# test_for_1_69.net
KiCad netlist of a schematic drawn in EasyEDA Pro
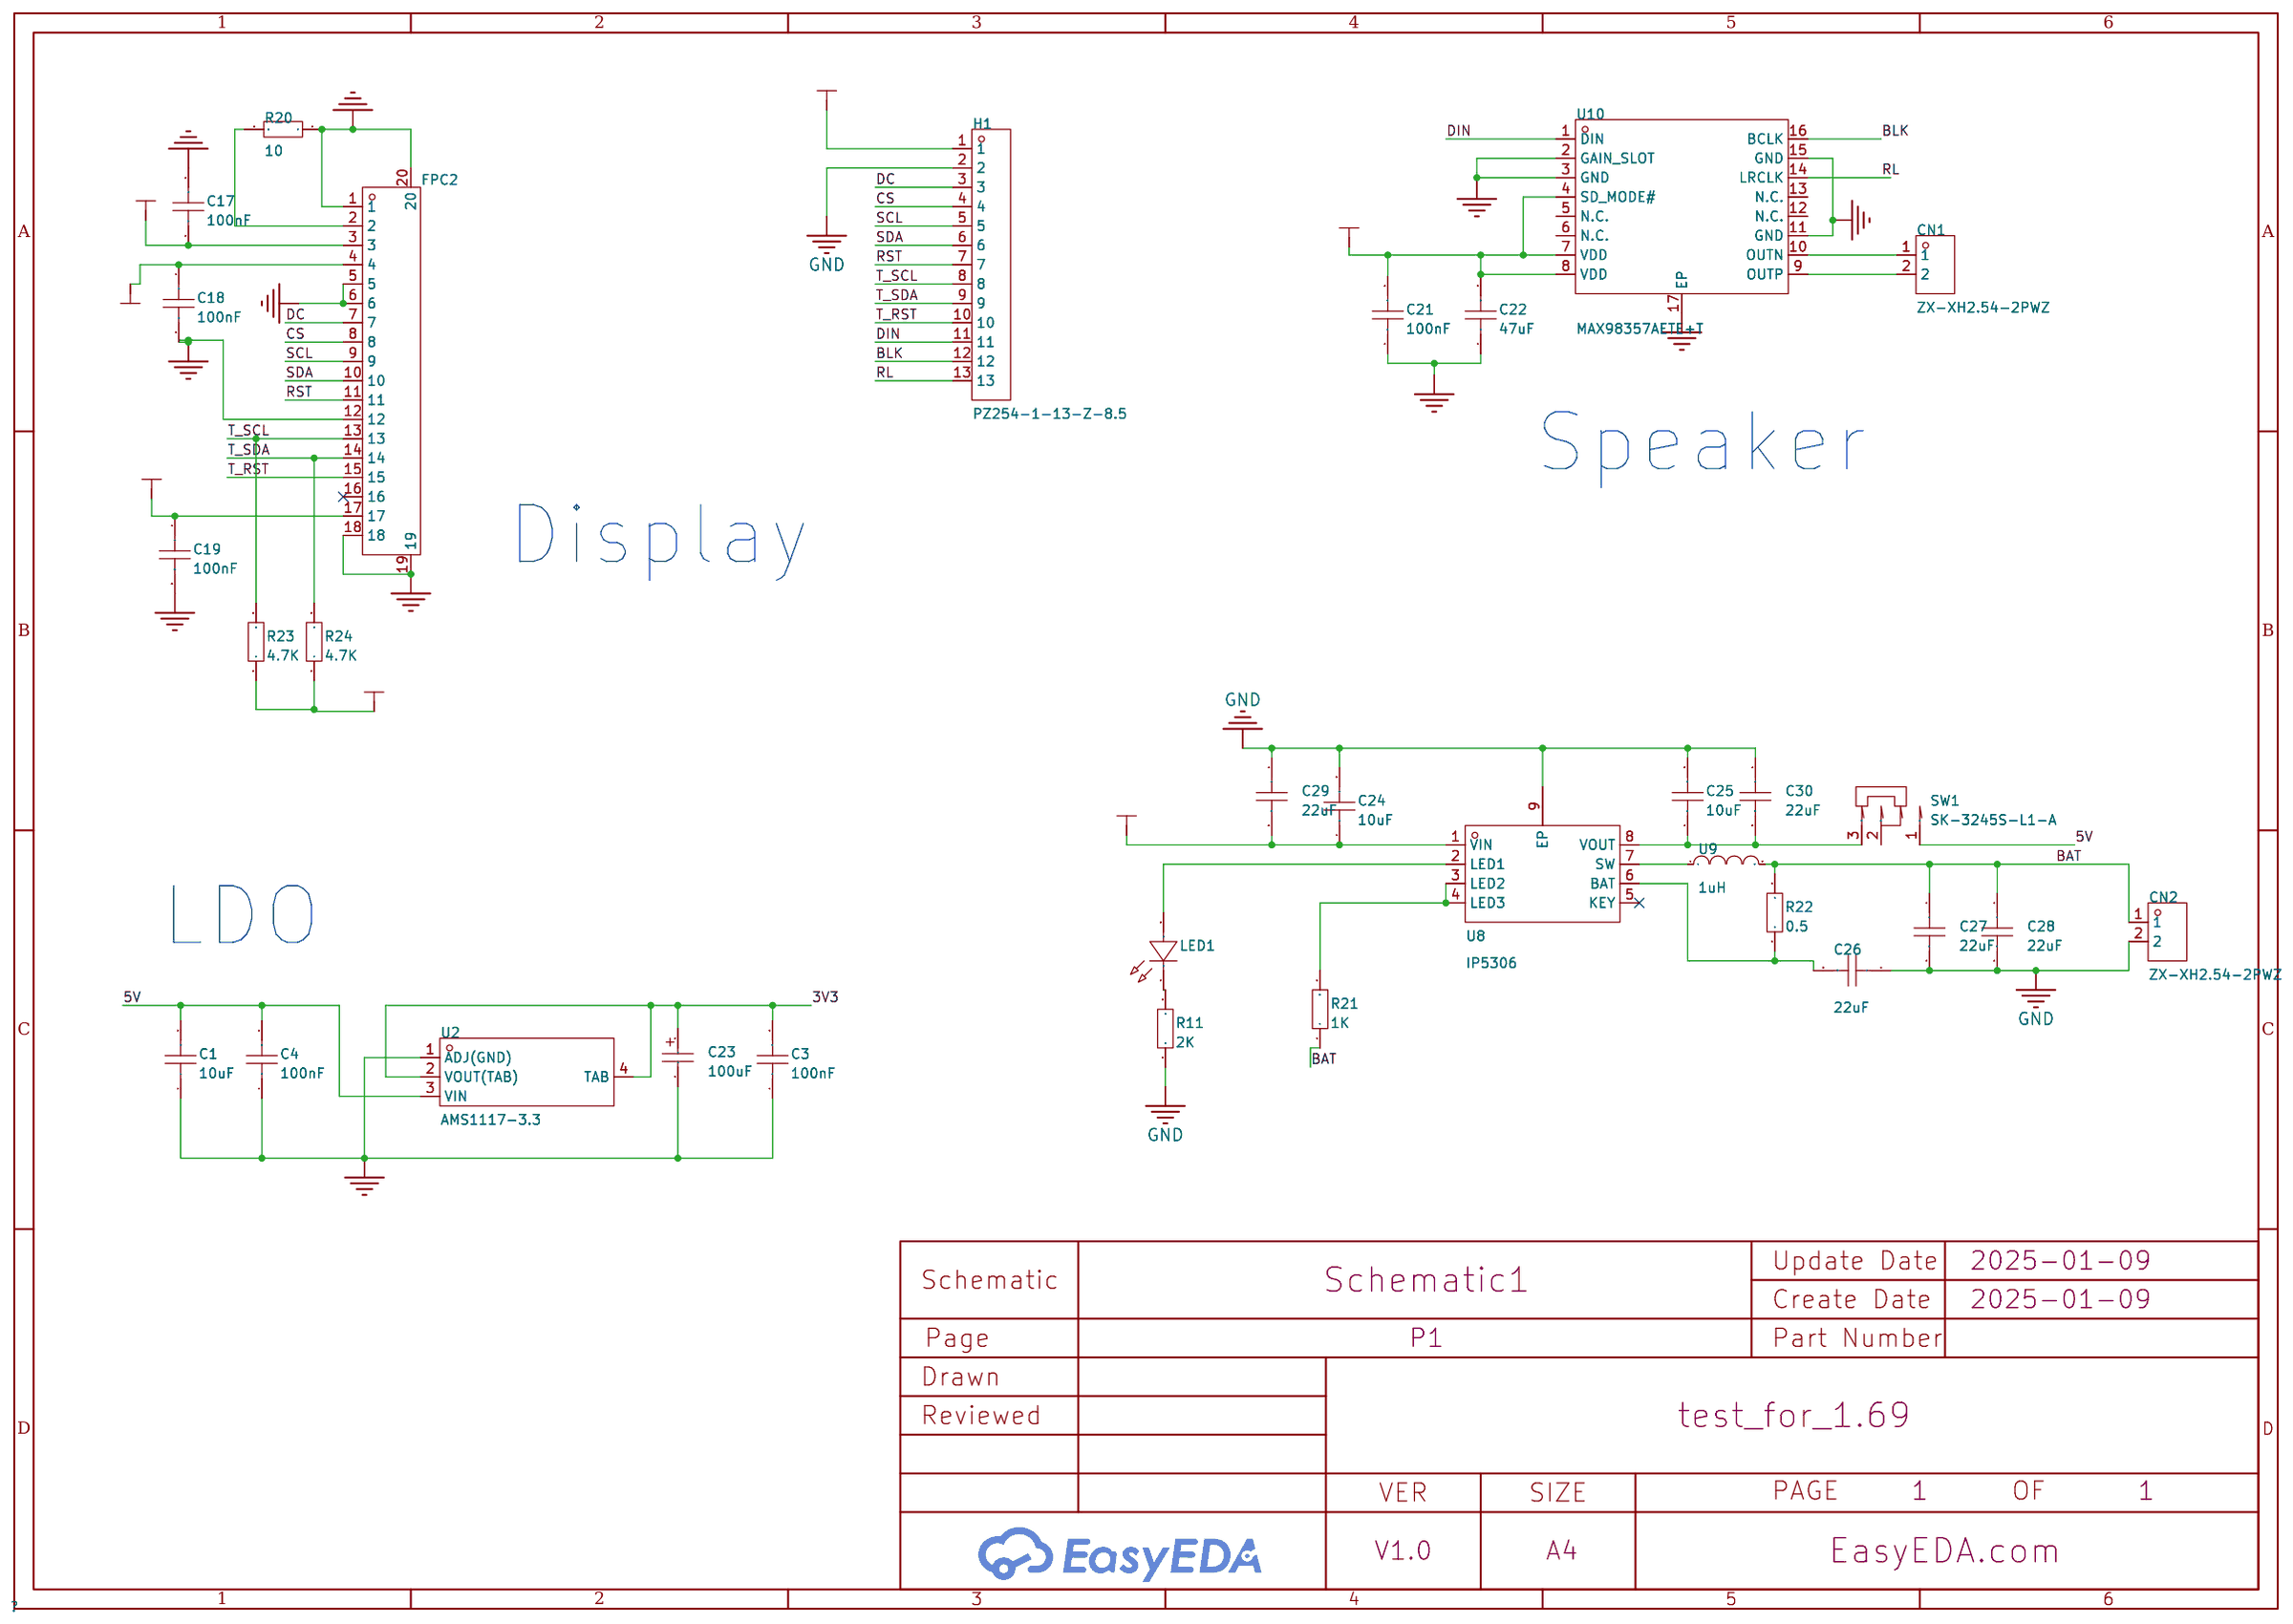
[diagram p0: schematic sheet]

(export (version "E")
  (design (tool "Eeschema 10.0.6"))
  (components
    (comp (ref "C1")
      (value "10uF")
      (footprint "easyedapro:C0603")
      (description "容值:10uF;精度:±10%;额定电压:10V;材质(温度系数):X5R;")
      (fields
        (field (name "Manufacturer Part") "CGA0603X5R106K100JT")
        (field (name "Manufacturer") "HRE(芯声)")
      )
      (libsource (lib "easyedapro") (part "CGA0603X5R106K100JT"))
    )
    (comp (ref "C3")
      (value "100nF")
      (footprint "easyedapro:C0402")
      (description "容值:100nF;精度:±10%;额定电压:16V;材质(温度系数):X7R;")
      (fields
        (field (name "Manufacturer Part") "CL05B104KO5NNNC")
        (field (name "Manufacturer") "SAMSUNG(三星)")
      )
      (libsource (lib "easyedapro") (part "CL05B104KO5NNNC"))
    )
    (comp (ref "C4")
      (value "100nF")
      (footprint "easyedapro:C0402")
      (description "容值:100nF;精度:±10%;额定电压:16V;材质(温度系数):X7R;")
      (fields
        (field (name "Manufacturer Part") "CL05B104KO5NNNC")
        (field (name "Manufacturer") "SAMSUNG(三星)")
      )
      (libsource (lib "easyedapro") (part "CL05B104KO5NNNC"))
    )
    (comp (ref "C17")
      (value "100nF")
      (footprint "easyedapro:C0402")
      (description "容值:100nF;精度:±10%;额定电压:16V;材质(温度系数):X7R;")
      (fields
        (field (name "Manufacturer Part") "CL05B104KO5NNNC")
        (field (name "Manufacturer") "SAMSUNG(三星)")
      )
      (libsource (lib "easyedapro") (part "CL05B104KO5NNNC"))
    )
    (comp (ref "C18")
      (value "100nF")
      (footprint "easyedapro:C0402")
      (description "容值:100nF;精度:±10%;额定电压:16V;材质(温度系数):X7R;")
      (fields
        (field (name "Manufacturer Part") "CL05B104KO5NNNC")
        (field (name "Manufacturer") "SAMSUNG(三星)")
      )
      (libsource (lib "easyedapro") (part "CL05B104KO5NNNC"))
    )
    (comp (ref "C19")
      (value "100nF")
      (footprint "easyedapro:C0402")
      (description "容值:100nF;精度:±10%;额定电压:16V;材质(温度系数):X7R;")
      (fields
        (field (name "Manufacturer Part") "CL05B104KO5NNNC")
        (field (name "Manufacturer") "SAMSUNG(三星)")
      )
      (libsource (lib "easyedapro") (part "CL05B104KO5NNNC"))
    )
    (comp (ref "C21")
      (value "100nF")
      (footprint "easyedapro:C0402")
      (description "容值:100nF;精度:±10%;额定电压:16V;材质(温度系数):X7R;")
      (fields
        (field (name "Manufacturer Part") "CL05B104KO5NNNC")
        (field (name "Manufacturer") "SAMSUNG(三星)")
      )
      (libsource (lib "easyedapro") (part "CL05B104KO5NNNC"))
    )
    (comp (ref "C22")
      (value "47uF")
      (footprint "easyedapro:C0603")
      (description "容值:47uF;精度:±20%;额定电压:6.3V;材质(温度系数):X5R;")
      (fields
        (field (name "Manufacturer Part") "CL10A476MQ8QRNC")
        (field (name "Manufacturer") "SAMSUNG(三星)")
      )
      (libsource (lib "easyedapro") (part "CL10A476MQ8QRNC"))
    )
    (comp (ref "C23")
      (value "100uF")
      (footprint "easyedapro:CASE-B_3528")
      (fields (field (name "Manufacturer Part") "TAJB107K006RNJ") (field (name "Manufacturer") "Kyocera AVX"))
      (libsource (lib "easyedapro") (part "TAJB107K006RNJ"))
    )
    (comp (ref "C24")
      (value "10uF")
      (footprint "easyedapro:C0603")
      (description "容值:10uF;精度:±10%;额定电压:10V;材质(温度系数):X5R;")
      (fields
        (field (name "Manufacturer Part") "CGA0603X5R106K100JT")
        (field (name "Manufacturer") "HRE(芯声)")
      )
      (libsource (lib "easyedapro") (part "CGA0603X5R106K100JT"))
    )
    (comp (ref "C25")
      (value "10uF")
      (footprint "easyedapro:C0603")
      (description "容值:10uF;精度:±10%;额定电压:10V;材质(温度系数):X5R;")
      (fields
        (field (name "Manufacturer Part") "CGA0603X5R106K100JT")
        (field (name "Manufacturer") "HRE(芯声)")
      )
      (libsource (lib "easyedapro") (part "CGA0603X5R106K100JT"))
    )
    (comp (ref "C26")
      (value "22uF")
      (footprint "easyedapro:C0603")
      (description "容值:10uF;精度:±10%;额定电压:10V;材质(温度系数):X5R;")
      (fields
        (field (name "Manufacturer Part") "CGA0603X5R106K100JT")
        (field (name "Manufacturer") "HRE(芯声)")
      )
      (libsource (lib "easyedapro") (part "CGA0603X5R106K100JT"))
    )
    (comp (ref "C27")
      (value "22uF")
      (footprint "easyedapro:C0603")
      (description "容值:10uF;精度:±10%;额定电压:10V;材质(温度系数):X5R;")
      (fields
        (field (name "Manufacturer Part") "CGA0603X5R106K100JT")
        (field (name "Manufacturer") "HRE(芯声)")
      )
      (libsource (lib "easyedapro") (part "CGA0603X5R106K100JT"))
    )
    (comp (ref "C28")
      (value "22uF")
      (footprint "easyedapro:C0603")
      (description "容值:10uF;精度:±10%;额定电压:10V;材质(温度系数):X5R;")
      (fields
        (field (name "Manufacturer Part") "CGA0603X5R106K100JT")
        (field (name "Manufacturer") "HRE(芯声)")
      )
      (libsource (lib "easyedapro") (part "CGA0603X5R106K100JT"))
    )
    (comp (ref "C29")
      (value "22uF")
      (footprint "easyedapro:C0603")
      (description "容值:10uF;精度:±10%;额定电压:10V;材质(温度系数):X5R;")
      (fields
        (field (name "Manufacturer Part") "CGA0603X5R106K100JT")
        (field (name "Manufacturer") "HRE(芯声)")
      )
      (libsource (lib "easyedapro") (part "CGA0603X5R106K100JT"))
    )
    (comp (ref "C30")
      (value "22uF")
      (footprint "easyedapro:C0603")
      (description "容值:10uF;精度:±10%;额定电压:10V;材质(温度系数):X5R;")
      (fields
        (field (name "Manufacturer Part") "CGA0603X5R106K100JT")
        (field (name "Manufacturer") "HRE(芯声)")
      )
      (libsource (lib "easyedapro") (part "CGA0603X5R106K100JT"))
    )
    (comp (ref "CN1")
      (value "ZX-XH2.54-2PWZ")
      (footprint "easyedapro:CONN-TH_2P-P2.50_ZX-XH2.54-2PWZ")
      (fields (field (name "Manufacturer") "Megastar(兆星)"))
      (libsource (lib "easyedapro") (part "ZX-XH2.54-2PWZ"))
    )
    (comp (ref "CN2")
      (value "ZX-XH2.54-2PWZ")
      (footprint "easyedapro:CONN-TH_2P-P2.50_ZX-XH2.54-2PWZ")
      (fields (field (name "Manufacturer") "Megastar(兆星)"))
      (libsource (lib "easyedapro") (part "ZX-XH2.54-2PWZ"))
    )
    (comp (ref "FPC2")
      (value "FPC-05F-18PH20")
      (footprint "easyedapro:FPC-SMD_18P-P0.50_FPC-05F-18PH20")
      (description "锁定特性:翻盖式;触点类型:下接;触点数量:18P;间距:0.5mm;安装类型:卧贴;工作温度范围:-25°C~+85°C;")
      (fields (field (name "Manufacturer") "XUNPU(讯普)"))
      (libsource (lib "easyedapro") (part "FPC-05F-18PH20"))
    )
    (comp (ref "H1")
      (value "PZ254-1-13-Z-8.5")
      (footprint "easyedapro:HDR-TH_13P-P2.54-V-M")
      (fields (field (name "Manufacturer") "HCTL(华灿天禄)"))
      (libsource (lib "easyedapro") (part "PZ254-1-13-Z-8.5"))
    )
    (comp (ref "LED1")
      (value "XL-1608SURC-06")
      (footprint "easyedapro:LED0603-RD_RED")
      (description "发光颜色:红色;功率:55mW;正向电流:25mA;主波长:617nm~621nm;透镜颜色:无色透明透镜;色温:-;发光角度:120°;载带方式:正贴;工作温度:-30°C~+85°C;")
      (fields (field (name "Manufacturer") "XINGLIGHT(成兴光)"))
      (libsource (lib "easyedapro") (part "XL-1608SURC-06"))
    )
    (comp (ref "R11")
      (value "2K")
      (footprint "easyedapro:R0402")
      (description "电阻类型:厚膜电阻;阻值:470Ω;精度:±1%;功率:62.5mW;最大工作电压:50V;温度系数:±100ppm/°C;")
      (fields
        (field (name "Manufacturer Part") "0402WGF4700TCE")
        (field (name "Manufacturer") "UNI-ROYAL(厚声)")
      )
      (libsource (lib "easyedapro") (part "0402WGF4700TCE"))
    )
    (comp (ref "R20")
      (value "10")
      (footprint "easyedapro:R0402")
      (description "电阻类型:厚膜电阻;阻值:470Ω;精度:±1%;功率:62.5mW;最大工作电压:50V;温度系数:±100ppm/°C;")
      (fields
        (field (name "Manufacturer Part") "0402WGF4700TCE")
        (field (name "Manufacturer") "UNI-ROYAL(厚声)")
      )
      (libsource (lib "easyedapro") (part "0402WGF4700TCE"))
    )
    (comp (ref "R21")
      (value "1K")
      (footprint "easyedapro:R0402")
      (description "电阻类型:厚膜电阻;阻值:470Ω;精度:±1%;功率:62.5mW;最大工作电压:50V;温度系数:±100ppm/°C;")
      (fields
        (field (name "Manufacturer Part") "0402WGF4700TCE")
        (field (name "Manufacturer") "UNI-ROYAL(厚声)")
      )
      (libsource (lib "easyedapro") (part "0402WGF4700TCE"))
    )
    (comp (ref "R22")
      (value "1K")
      (footprint "easyedapro:R0402")
      (description "电阻类型:厚膜电阻;阻值:470Ω;精度:±1%;功率:62.5mW;最大工作电压:50V;温度系数:±100ppm/°C;")
      (fields
        (field (name "Manufacturer Part") "0402WGF4700TCE")
        (field (name "Manufacturer") "UNI-ROYAL(厚声)")
      )
      (libsource (lib "easyedapro") (part "0402WGF4700TCE"))
    )
    (comp (ref "R23")
      (value "4.7K")
      (footprint "easyedapro:R0402")
      (description "电阻类型:厚膜电阻;阻值:470Ω;精度:±1%;功率:62.5mW;最大工作电压:50V;温度系数:±100ppm/°C;")
      (fields
        (field (name "Manufacturer Part") "0402WGF4700TCE")
        (field (name "Manufacturer") "UNI-ROYAL(厚声)")
      )
      (libsource (lib "easyedapro") (part "0402WGF4700TCE"))
    )
    (comp (ref "R24")
      (value "4.7K")
      (footprint "easyedapro:R0402")
      (description "电阻类型:厚膜电阻;阻值:470Ω;精度:±1%;功率:62.5mW;最大工作电压:50V;温度系数:±100ppm/°C;")
      (fields
        (field (name "Manufacturer Part") "0402WGF4700TCE")
        (field (name "Manufacturer") "UNI-ROYAL(厚声)")
      )
      (libsource (lib "easyedapro") (part "0402WGF4700TCE"))
    )
    (comp (ref "SW1")
      (value "SK-3245S-L1-A")
      (footprint "easyedapro:SW-SMD_SK-3245S-L1-A-1")
      (fields (field (name "Manufacturer") "XKB Connection(中国星坤)"))
      (libsource (lib "easyedapro") (part "SK-3245S-L1-A"))
    )
    (comp (ref "U2")
      (value "AMS1117-3.3")
      (footprint "easyedapro:SOT-223-4_L6.5-W3.5-P2.30-LS7.0-BR")
      (description "输出类型:固定;工作电压:12V;输出电压:3.3V;输出电流:1A;电源纹波抑制比(PSRR):60dB@(120Hz);输出极性:正极;")
      (fields (field (name "Manufacturer") "UMW(友台半导体)"))
      (libsource (lib "easyedapro") (part "AMS1117-3.3_C347222"))
    )
    (comp (ref "U8")
      (value "IP5306")
      (footprint "easyedapro:ESOP-8_L4.9-W3.9-P1.27-LS6.0-BL-EP")
      (fields (field (name "Manufacturer") "INJOINIC(英集芯)"))
      (libsource (lib "easyedapro") (part "IP5306"))
    )
    (comp (ref "U9")
      (value "1uH")
      (footprint "easyedapro:IND-SMD_L2.5-W2.0_YXNAQ252010-3R3M")
      (fields (field (name "Manufacturer Part") "IND\\L2.5XW"))
      (libsource (lib "easyedapro") (part "IND{backslash}L2.5XW"))
    )
    (comp (ref "U10")
      (value "MAX98357AETE+T")
      (footprint "easyedapro:TQFN-16_L3.0-W3.0-P0.50-BL-EP1.5")
      (description "功放类型:-;扬声器通道数:单声道;输出功率:3.2Wx2@4Ω;")
      (fields (field (name "Manufacturer") "ADI(亚德诺)/MAXIM(美信)"))
      (libsource (lib "easyedapro") (part "MAX98357AETE+T"))
    )
  )
  (nets
    (net (code "1") (name "/5V") (class "Default")
      (node (ref "C1") (pin "2") (pinfunction "2_2") (pintype "unspecified"))
      (node (ref "C4") (pin "2") (pinfunction "2_2") (pintype "unspecified"))
      (node (ref "SW1") (pin "1") (pinfunction "1_1") (pintype "unspecified"))
      (node (ref "U2") (pin "3") (pinfunction "VIN_3") (pintype "unspecified"))
    )
    (net (code "2") (name "/BAT") (class "Default")
      (node (ref "C27") (pin "1") (pinfunction "1_1") (pintype "unspecified"))
      (node (ref "C28") (pin "1") (pinfunction "1_1") (pintype "unspecified"))
      (node (ref "CN2") (pin "1") (pinfunction "1_1") (pintype "unspecified"))
      (node (ref "R21") (pin "1") (pinfunction "1_1") (pintype "input"))
      (node (ref "R22") (pin "2") (pinfunction "2_2") (pintype "input"))
      (node (ref "U9") (pin "2") (pinfunction "2_2") (pintype "unspecified"))
    )
    (net (code "3") (name "/BLK") (class "Default")
      (node (ref "H1") (pin "12") (pinfunction "12_12") (pintype "unspecified"))
      (node (ref "U10") (pin "16") (pinfunction "BCLK_16") (pintype "unspecified"))
    )
    (net (code "4") (name "/CS") (class "Default")
      (node (ref "FPC2") (pin "8") (pinfunction "8_8") (pintype "unspecified"))
      (node (ref "H1") (pin "4") (pinfunction "4_4") (pintype "unspecified"))
    )
    (net (code "5") (name "/DC") (class "Default")
      (node (ref "FPC2") (pin "7") (pinfunction "7_7") (pintype "unspecified"))
      (node (ref "H1") (pin "3") (pinfunction "3_3") (pintype "unspecified"))
    )
    (net (code "6") (name "/DIN") (class "Default")
      (node (ref "H1") (pin "11") (pinfunction "11_11") (pintype "unspecified"))
      (node (ref "U10") (pin "1") (pinfunction "DIN_1") (pintype "unspecified"))
    )
    (net (code "7") (name "/RL") (class "Default")
      (node (ref "H1") (pin "13") (pinfunction "13_13") (pintype "unspecified"))
      (node (ref "U10") (pin "14") (pinfunction "LRCLK_14") (pintype "unspecified"))
    )
    (net (code "8") (name "/RST") (class "Default")
      (node (ref "FPC2") (pin "11") (pinfunction "11_11") (pintype "unspecified"))
      (node (ref "H1") (pin "7") (pinfunction "7_7") (pintype "unspecified"))
    )
    (net (code "9") (name "/SCL") (class "Default")
      (node (ref "FPC2") (pin "9") (pinfunction "9_9") (pintype "unspecified"))
      (node (ref "H1") (pin "5") (pinfunction "5_5") (pintype "unspecified"))
    )
    (net (code "10") (name "/SDA") (class "Default")
      (node (ref "FPC2") (pin "10") (pinfunction "10_10") (pintype "unspecified"))
      (node (ref "H1") (pin "6") (pinfunction "6_6") (pintype "unspecified"))
    )
    (net (code "11") (name "/T_RST") (class "Default")
      (node (ref "FPC2") (pin "15") (pinfunction "15_15") (pintype "unspecified"))
      (node (ref "H1") (pin "10") (pinfunction "10_10") (pintype "unspecified"))
    )
    (net (code "12") (name "/T_SCL") (class "Default")
      (node (ref "FPC2") (pin "13") (pinfunction "13_13") (pintype "unspecified"))
      (node (ref "H1") (pin "8") (pinfunction "8_8") (pintype "unspecified"))
      (node (ref "R23") (pin "2") (pinfunction "2_2") (pintype "input"))
    )
    (net (code "13") (name "/T_SDA") (class "Default")
      (node (ref "FPC2") (pin "14") (pinfunction "14_14") (pintype "unspecified"))
      (node (ref "H1") (pin "9") (pinfunction "9_9") (pintype "unspecified"))
      (node (ref "R24") (pin "2") (pinfunction "2_2") (pintype "input"))
    )
    (net (code "14") (name "3V3") (class "Default")
      (node (ref "C17") (pin "2") (pinfunction "2_2") (pintype "unspecified"))
      (node (ref "C18") (pin "1") (pinfunction "1_1") (pintype "unspecified"))
      (node (ref "C19") (pin "1") (pinfunction "1_1") (pintype "unspecified"))
      (node (ref "C21") (pin "2") (pinfunction "2_2") (pintype "unspecified"))
      (node (ref "C22") (pin "2") (pinfunction "2_2") (pintype "unspecified"))
      (node (ref "C23") (pin "1") (pinfunction "1_1") (pintype "input"))
      (node (ref "C3") (pin "2") (pinfunction "2_2") (pintype "unspecified"))
      (node (ref "FPC2") (pin "17") (pinfunction "17_17") (pintype "unspecified"))
      (node (ref "FPC2") (pin "3") (pinfunction "3_3") (pintype "unspecified"))
      (node (ref "FPC2") (pin "4") (pinfunction "4_4") (pintype "unspecified"))
      (node (ref "R23") (pin "1") (pinfunction "1_1") (pintype "input"))
      (node (ref "R24") (pin "1") (pinfunction "1_1") (pintype "input"))
      (node (ref "U10") (pin "4") (pinfunction "SD_MODE#_4") (pintype "unspecified"))
      (node (ref "U10") (pin "7") (pinfunction "VDD_7") (pintype "unspecified"))
      (node (ref "U10") (pin "8") (pinfunction "VDD_8") (pintype "unspecified"))
      (node (ref "U2") (pin "2") (pinfunction "VOUT(TAB)_2") (pintype "unspecified"))
      (node (ref "U2") (pin "4") (pinfunction "TAB_4") (pintype "unspecified"))
    )
    (net (code "15") (name "5V_IN") (class "Default")
      (node (ref "C24") (pin "1") (pinfunction "1_1") (pintype "unspecified"))
      (node (ref "C29") (pin "2") (pinfunction "2_2") (pintype "unspecified"))
      (node (ref "H1") (pin "1") (pinfunction "1_1") (pintype "unspecified"))
      (node (ref "U8") (pin "1") (pinfunction "VIN_1") (pintype "unspecified"))
    )
    (net (code "16") (name "GND") (class "Default")
      (node (ref "C1") (pin "1") (pinfunction "1_1") (pintype "unspecified"))
      (node (ref "C17") (pin "1") (pinfunction "1_1") (pintype "unspecified"))
      (node (ref "C18") (pin "2") (pinfunction "2_2") (pintype "unspecified"))
      (node (ref "C19") (pin "2") (pinfunction "2_2") (pintype "unspecified"))
      (node (ref "C21") (pin "1") (pinfunction "1_1") (pintype "unspecified"))
      (node (ref "C22") (pin "1") (pinfunction "1_1") (pintype "unspecified"))
      (node (ref "C23") (pin "2") (pinfunction "2_2") (pintype "input"))
      (node (ref "C24") (pin "2") (pinfunction "2_2") (pintype "unspecified"))
      (node (ref "C25") (pin "2") (pinfunction "2_2") (pintype "unspecified"))
      (node (ref "C26") (pin "1") (pinfunction "1_1") (pintype "unspecified"))
      (node (ref "C27") (pin "2") (pinfunction "2_2") (pintype "unspecified"))
      (node (ref "C28") (pin "2") (pinfunction "2_2") (pintype "unspecified"))
      (node (ref "C29") (pin "1") (pinfunction "1_1") (pintype "unspecified"))
      (node (ref "C3") (pin "1") (pinfunction "1_1") (pintype "unspecified"))
      (node (ref "C30") (pin "1") (pinfunction "1_1") (pintype "unspecified"))
      (node (ref "C4") (pin "1") (pinfunction "1_1") (pintype "unspecified"))
      (node (ref "CN2") (pin "2") (pinfunction "2_2") (pintype "unspecified"))
      (node (ref "FPC2") (pin "1") (pinfunction "1_1") (pintype "unspecified"))
      (node (ref "FPC2") (pin "12") (pinfunction "12_12") (pintype "unspecified"))
      (node (ref "FPC2") (pin "18") (pinfunction "18_18") (pintype "unspecified"))
      (node (ref "FPC2") (pin "19") (pinfunction "19_19") (pintype "unspecified"))
      (node (ref "FPC2") (pin "20") (pinfunction "20_20") (pintype "unspecified"))
      (node (ref "FPC2") (pin "5") (pinfunction "5_5") (pintype "unspecified"))
      (node (ref "FPC2") (pin "6") (pinfunction "6_6") (pintype "unspecified"))
      (node (ref "H1") (pin "2") (pinfunction "2_2") (pintype "unspecified"))
      (node (ref "R11") (pin "1") (pinfunction "1_1") (pintype "input"))
      (node (ref "R20") (pin "1") (pinfunction "1_1") (pintype "input"))
      (node (ref "U10") (pin "11") (pinfunction "GND_11") (pintype "unspecified"))
      (node (ref "U10") (pin "15") (pinfunction "GND_15") (pintype "unspecified"))
      (node (ref "U10") (pin "17") (pinfunction "EP_17") (pintype "unspecified"))
      (node (ref "U10") (pin "2") (pinfunction "GAIN_SLOT_2") (pintype "unspecified"))
      (node (ref "U10") (pin "3") (pinfunction "GND_3") (pintype "unspecified"))
      (node (ref "U2") (pin "1") (pinfunction "ADJ(GND)_1") (pintype "unspecified"))
      (node (ref "U8") (pin "9") (pinfunction "EP_9") (pintype "unspecified"))
    )
    (net (code "17") (name "Net-(FPC2-Pad2)") (class "Default")
      (node (ref "FPC2") (pin "2") (pinfunction "2_2") (pintype "unspecified"))
      (node (ref "R20") (pin "2") (pinfunction "2_2") (pintype "input"))
    )
    (net (code "18") (name "Net-(LED1-A)") (class "Default")
      (node (ref "LED1") (pin "2") (pinfunction "A_2") (pintype "unspecified"))
      (node (ref "U8") (pin "2") (pinfunction "LED1_2") (pintype "unspecified"))
    )
    (net (code "19") (name "Net-(LED1-K)") (class "Default")
      (node (ref "LED1") (pin "1") (pinfunction "K_1") (pintype "unspecified"))
      (node (ref "R11") (pin "2") (pinfunction "2_2") (pintype "input"))
    )
    (net (code "20") (name "Net-(U8-BAT)") (class "Default")
      (node (ref "C26") (pin "2") (pinfunction "2_2") (pintype "unspecified"))
      (node (ref "R22") (pin "1") (pinfunction "1_1") (pintype "input"))
      (node (ref "U8") (pin "6") (pinfunction "BAT_6") (pintype "unspecified"))
    )
    (net (code "21") (name "Net-(U8-LED2)") (class "Default")
      (node (ref "R21") (pin "2") (pinfunction "2_2") (pintype "input"))
      (node (ref "U8") (pin "3") (pinfunction "LED2_3") (pintype "unspecified"))
      (node (ref "U8") (pin "4") (pinfunction "LED3_4") (pintype "unspecified"))
    )
    (net (code "22") (name "Net-(U8-SW)") (class "Default")
      (node (ref "U8") (pin "7") (pinfunction "SW_7") (pintype "unspecified"))
      (node (ref "U9") (pin "1") (pinfunction "1_1") (pintype "unspecified"))
    )
    (net (code "23") (name "Net-(U8-VOUT)") (class "Default")
      (node (ref "C25") (pin "1") (pinfunction "1_1") (pintype "unspecified"))
      (node (ref "C30") (pin "2") (pinfunction "2_2") (pintype "unspecified"))
      (node (ref "SW1") (pin "3") (pinfunction "3_3") (pintype "unspecified"))
      (node (ref "U8") (pin "8") (pinfunction "VOUT_8") (pintype "unspecified"))
    )
    (net (code "24") (name "Net-(U10-OUTN)") (class "Default")
      (node (ref "CN1") (pin "1") (pinfunction "1_1") (pintype "unspecified"))
      (node (ref "U10") (pin "10") (pinfunction "OUTN_10") (pintype "unspecified"))
    )
    (net (code "25") (name "Net-(U10-OUTP)") (class "Default")
      (node (ref "CN1") (pin "2") (pinfunction "2_2") (pintype "unspecified"))
      (node (ref "U10") (pin "9") (pinfunction "OUTP_9") (pintype "unspecified"))
    )
    (net (code "26") (name "unconnected-(FPC2-Pad16)") (class "Default")
      (node (ref "FPC2") (pin "16") (pinfunction "16_16") (pintype "unspecified+no_connect"))
    )
    (net (code "27") (name "unconnected-(SW1-Pad2)") (class "Default")
      (node (ref "SW1") (pin "2") (pinfunction "2_2") (pintype "unspecified"))
    )
    (net (code "28") (name "unconnected-(U8-KEY-Pad5)") (class "Default")
      (node (ref "U8") (pin "5") (pinfunction "KEY_5") (pintype "unspecified+no_connect"))
    )
    (net (code "29") (name "unconnected-(U10-N.C.-Pad5)") (class "Default")
      (node (ref "U10") (pin "5") (pinfunction "N.C._5") (pintype "unspecified"))
    )
    (net (code "30") (name "unconnected-(U10-N.C.-Pad6)") (class "Default")
      (node (ref "U10") (pin "6") (pinfunction "N.C._6") (pintype "unspecified"))
    )
    (net (code "31") (name "unconnected-(U10-N.C.-Pad12)") (class "Default")
      (node (ref "U10") (pin "12") (pinfunction "N.C._12") (pintype "unspecified"))
    )
    (net (code "32") (name "unconnected-(U10-N.C.-Pad13)") (class "Default")
      (node (ref "U10") (pin "13") (pinfunction "N.C._13") (pintype "unspecified"))
    )
  )
)
